# RS485_Multiplexer.net
KiCad netlist of a schematic drawn in Altium Designer
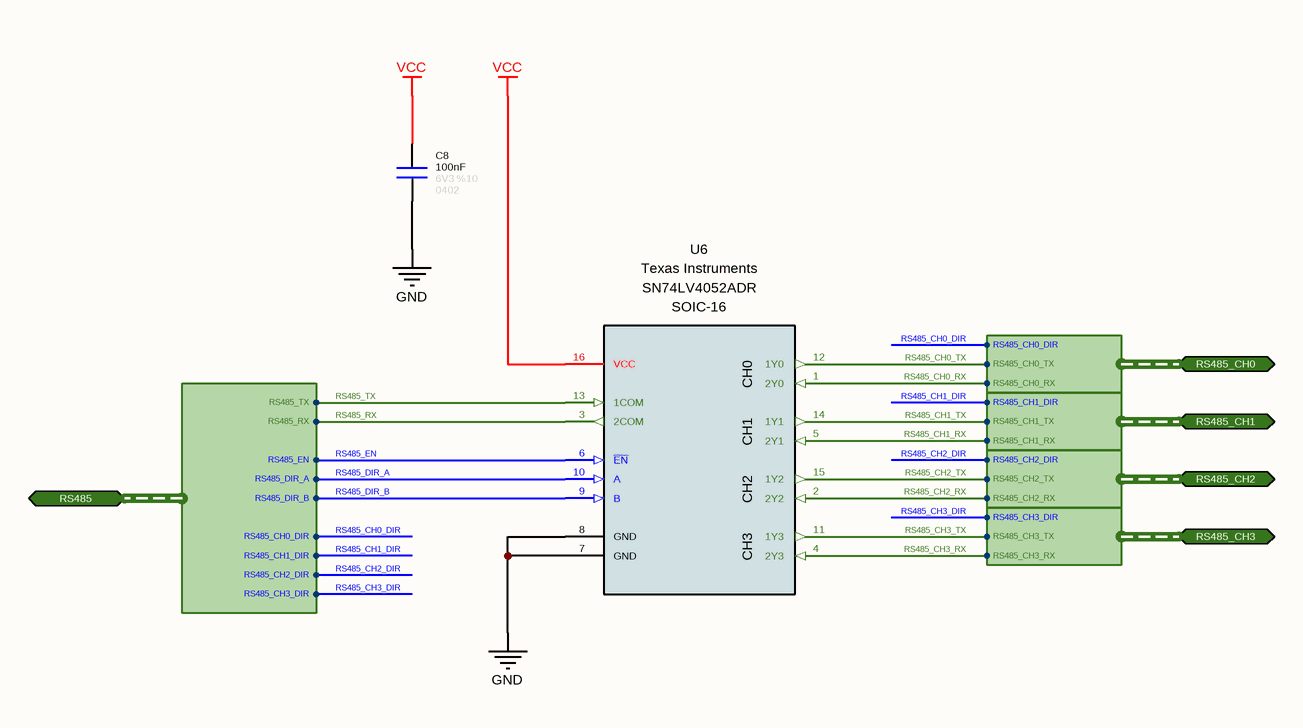
[diagram p0: RS485 Multiplexer.SchDoc]

(export (version "E")
  (design (tool "Eeschema 10.0.6"))
  (components
    (comp (ref "C8")
      (value "100nF")
      (footprint "CAPACITOR_0402")
      (description "Capacitor - 100nF [0402-6V3] (Ceramic)")
      (fields
        (field (name "MANUFACTURER PART NUMBER") "04026D104KAT4A")
        (field (name "TOLERANCE") "%10")
        (field (name "VOLTAGE") "6V3")
        (field (name "CASE") "0402")
        (field (name "Comment") "Capacitor - 100nF [0402] (Ceramic)")
      )
      (libsource (lib "P101DA_Library") (part "Capacitor - 100nF [0402-6V3]"))
    )
    (comp (ref "U6")
      (value "SN74LV4052ADR")
      (footprint "SOIC-16 Narrow")
      (description "Multiplexer Switch ICs Dual 4-Ch Analog Mltplxr/Demltplxr")
      (fields
        (field (name "MANUFACTURER NAME") "Texas Instruments")
        (field (name "MANUFACTURER PART NUMBER") "SN74LV4052ADR")
        (field (name "CASE") "SOIC-16")
      )
      (libsource (lib "P101DA_Library") (part "IC - SN74LV4052ADR"))
    )
  )
  (nets
    (net (code "7") (name "/RS485_CH0_RX") (class "Default")
      (node (ref "U6") (pin "1") (pinfunction "2Y0_1") (pintype "input"))
    )
    (net (code "8") (name "/RS485_CH0_TX") (class "Default")
      (node (ref "U6") (pin "12") (pinfunction "1Y0_12") (pintype "output"))
    )
    (net (code "10") (name "/RS485_CH1_RX") (class "Default")
      (node (ref "U6") (pin "5") (pinfunction "2Y1_5") (pintype "input"))
    )
    (net (code "11") (name "/RS485_CH1_TX") (class "Default")
      (node (ref "U6") (pin "14") (pinfunction "1Y1_14") (pintype "output"))
    )
    (net (code "13") (name "/RS485_CH2_RX") (class "Default")
      (node (ref "U6") (pin "2") (pinfunction "2Y2_2") (pintype "input"))
    )
    (net (code "14") (name "/RS485_CH2_TX") (class "Default")
      (node (ref "U6") (pin "15") (pinfunction "1Y2_15") (pintype "output"))
    )
    (net (code "16") (name "/RS485_CH3_RX") (class "Default")
      (node (ref "U6") (pin "4") (pinfunction "2Y3_4") (pintype "input"))
    )
    (net (code "17") (name "/RS485_CH3_TX") (class "Default")
      (node (ref "U6") (pin "11") (pinfunction "1Y3_11") (pintype "output"))
    )
    (net (code "18") (name "/RS485_DIR_A") (class "Default")
      (node (ref "U6") (pin "10") (pinfunction "A_10") (pintype "input"))
    )
    (net (code "19") (name "/RS485_DIR_B") (class "Default")
      (node (ref "U6") (pin "9") (pinfunction "B_9") (pintype "input"))
    )
    (net (code "20") (name "/RS485_EN") (class "Default")
      (node (ref "U6") (pin "6") (pinfunction "~{EN}_6") (pintype "input"))
    )
    (net (code "21") (name "/RS485_RX") (class "Default")
      (node (ref "U6") (pin "3") (pinfunction "2COM_3") (pintype "output"))
    )
    (net (code "22") (name "/RS485_TX") (class "Default")
      (node (ref "U6") (pin "13") (pinfunction "1COM_13") (pintype "input"))
    )
    (net (code "28") (name "GND") (class "Default")
      (node (ref "C8") (pin "1") (pinfunction "1_1") (pintype "passive"))
      (node (ref "U6") (pin "7") (pinfunction "GND_7") (pintype "power_in"))
      (node (ref "U6") (pin "8") (pinfunction "GND_8") (pintype "power_in"))
    )
    (net (code "29") (name "VCC") (class "Default")
      (node (ref "C8") (pin "2") (pinfunction "2_2") (pintype "passive"))
      (node (ref "U6") (pin "16") (pinfunction "VCC_16") (pintype "power_in"))
    )
  )
)
